# Quad-Stage-Prototype_FPGA_V1_0.net
KiCad netlist of a schematic drawn in Altium Designer
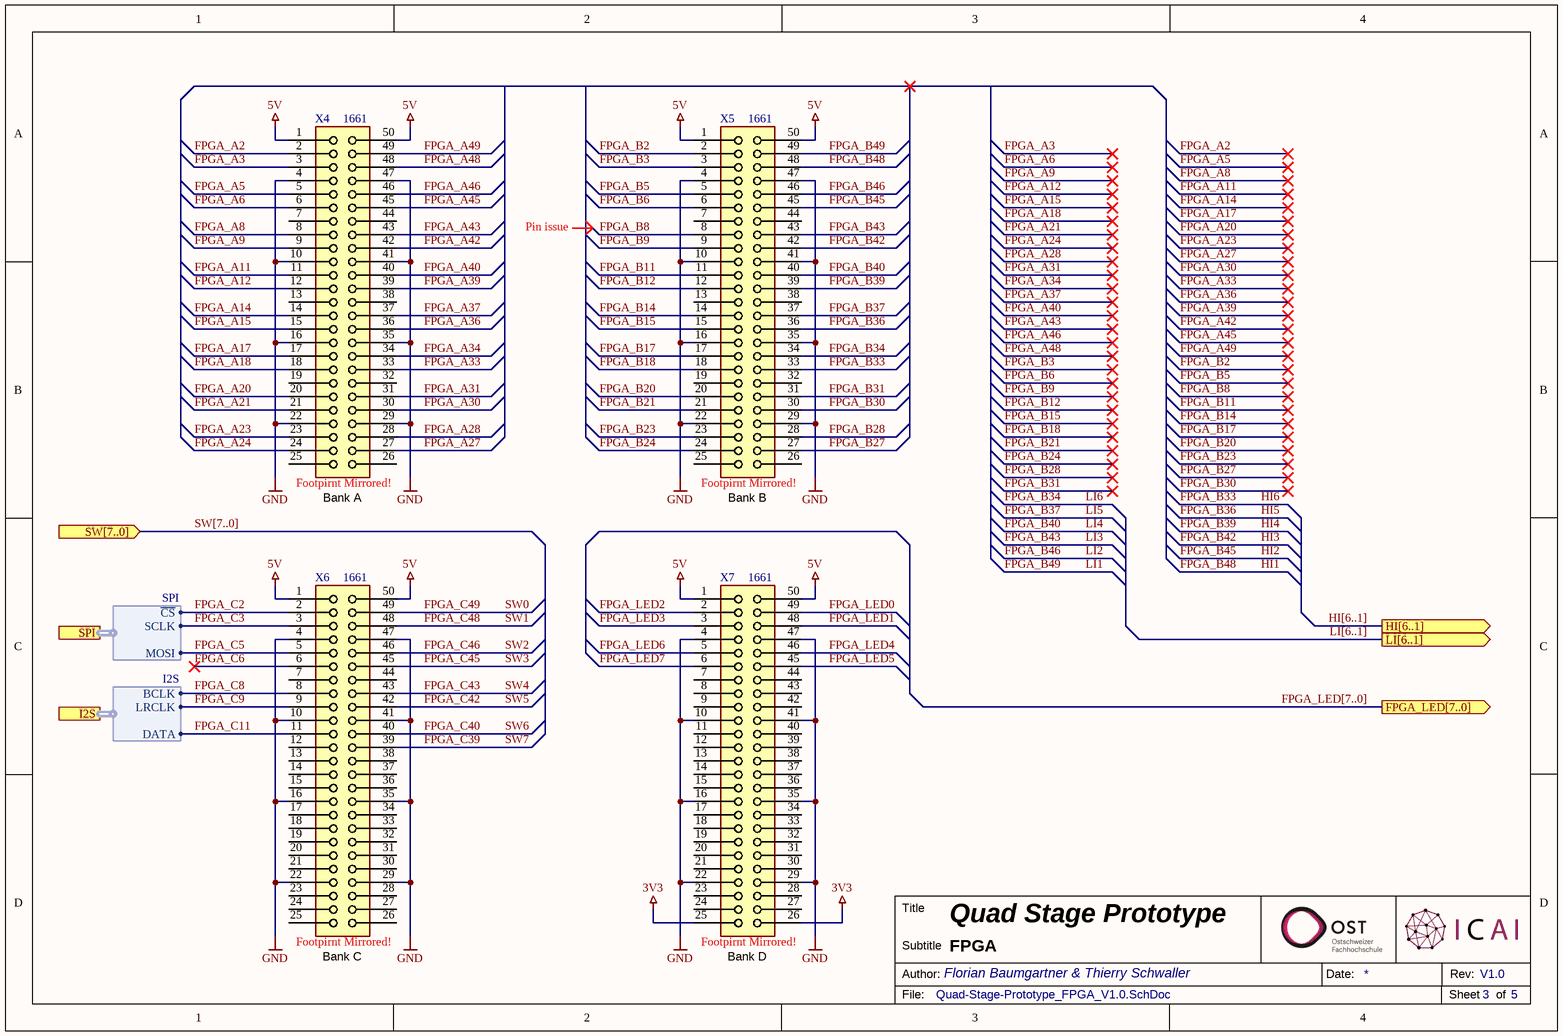
[diagram p0: Quad-Stage-Prototype_FPGA_V1.0.SchDoc]

(export (version "E")
  (design (tool "Eeschema 10.0.6"))
  (components
    (comp (ref "X4")
      (value "1661")
      (footprint "SMD Connector (1661)")
      (description "Board-to-Board Connector (Receptacle)")
      (libsource (lib "Quad-Stage-Prototype") (part "X-4UCON_1661"))
    )
    (comp (ref "X5")
      (value "1661")
      (footprint "SMD Connector (1661)")
      (description "Board-to-Board Connector (Receptacle)")
      (libsource (lib "Quad-Stage-Prototype") (part "X-4UCON_1661"))
    )
    (comp (ref "X6")
      (value "1661")
      (footprint "SMD Connector (1661)")
      (description "Board-to-Board Connector (Receptacle)")
      (libsource (lib "Quad-Stage-Prototype") (part "X-4UCON_1661"))
    )
    (comp (ref "X7")
      (value "1661")
      (footprint "SMD Connector (1661)")
      (description "Board-to-Board Connector (Receptacle)")
      (libsource (lib "Quad-Stage-Prototype") (part "X-4UCON_1661"))
    )
  )
  (nets
    (net (code "3") (name "/FPGA_A2") (class "Default")
      (node (ref "X4") (pin "2") (pinfunction "2_2") (pintype "passive"))
    )
    (net (code "4") (name "/FPGA_A3") (class "Default")
      (node (ref "X4") (pin "3") (pinfunction "3_3") (pintype "passive"))
    )
    (net (code "5") (name "/FPGA_A5") (class "Default")
      (node (ref "X4") (pin "5") (pinfunction "5_5") (pintype "passive"))
    )
    (net (code "6") (name "/FPGA_A6") (class "Default")
      (node (ref "X4") (pin "6") (pinfunction "6_6") (pintype "passive"))
    )
    (net (code "7") (name "/FPGA_A8") (class "Default")
      (node (ref "X4") (pin "8") (pinfunction "8_8") (pintype "passive"))
    )
    (net (code "8") (name "/FPGA_A9") (class "Default")
      (node (ref "X4") (pin "9") (pinfunction "9_9") (pintype "passive"))
    )
    (net (code "9") (name "/FPGA_A11") (class "Default")
      (node (ref "X4") (pin "11") (pinfunction "11_11") (pintype "passive"))
    )
    (net (code "10") (name "/FPGA_A12") (class "Default")
      (node (ref "X4") (pin "12") (pinfunction "12_12") (pintype "passive"))
    )
    (net (code "11") (name "/FPGA_A14") (class "Default")
      (node (ref "X4") (pin "14") (pinfunction "14_14") (pintype "passive"))
    )
    (net (code "12") (name "/FPGA_A15") (class "Default")
      (node (ref "X4") (pin "15") (pinfunction "15_15") (pintype "passive"))
    )
    (net (code "13") (name "/FPGA_A17") (class "Default")
      (node (ref "X4") (pin "17") (pinfunction "17_17") (pintype "passive"))
    )
    (net (code "14") (name "/FPGA_A18") (class "Default")
      (node (ref "X4") (pin "18") (pinfunction "18_18") (pintype "passive"))
    )
    (net (code "15") (name "/FPGA_A20") (class "Default")
      (node (ref "X4") (pin "20") (pinfunction "20_20") (pintype "passive"))
    )
    (net (code "16") (name "/FPGA_A21") (class "Default")
      (node (ref "X4") (pin "21") (pinfunction "21_21") (pintype "passive"))
    )
    (net (code "17") (name "/FPGA_A23") (class "Default")
      (node (ref "X4") (pin "23") (pinfunction "23_23") (pintype "passive"))
    )
    (net (code "18") (name "/FPGA_A24") (class "Default")
      (node (ref "X4") (pin "24") (pinfunction "24_24") (pintype "passive"))
    )
    (net (code "19") (name "/FPGA_A27") (class "Default")
      (node (ref "X4") (pin "27") (pinfunction "27_27") (pintype "passive"))
    )
    (net (code "20") (name "/FPGA_A28") (class "Default")
      (node (ref "X4") (pin "28") (pinfunction "28_28") (pintype "passive"))
    )
    (net (code "21") (name "/FPGA_A30") (class "Default")
      (node (ref "X4") (pin "30") (pinfunction "30_30") (pintype "passive"))
    )
    (net (code "22") (name "/FPGA_A31") (class "Default")
      (node (ref "X4") (pin "31") (pinfunction "31_31") (pintype "passive"))
    )
    (net (code "23") (name "/FPGA_A33") (class "Default")
      (node (ref "X4") (pin "33") (pinfunction "33_33") (pintype "passive"))
    )
    (net (code "24") (name "/FPGA_A34") (class "Default")
      (node (ref "X4") (pin "34") (pinfunction "34_34") (pintype "passive"))
    )
    (net (code "25") (name "/FPGA_A36") (class "Default")
      (node (ref "X4") (pin "36") (pinfunction "36_36") (pintype "passive"))
    )
    (net (code "26") (name "/FPGA_A37") (class "Default")
      (node (ref "X4") (pin "37") (pinfunction "37_37") (pintype "passive"))
    )
    (net (code "27") (name "/FPGA_A39") (class "Default")
      (node (ref "X4") (pin "39") (pinfunction "39_39") (pintype "passive"))
    )
    (net (code "28") (name "/FPGA_A40") (class "Default")
      (node (ref "X4") (pin "40") (pinfunction "40_40") (pintype "passive"))
    )
    (net (code "29") (name "/FPGA_A42") (class "Default")
      (node (ref "X4") (pin "42") (pinfunction "42_42") (pintype "passive"))
    )
    (net (code "30") (name "/FPGA_A43") (class "Default")
      (node (ref "X4") (pin "43") (pinfunction "43_43") (pintype "passive"))
    )
    (net (code "31") (name "/FPGA_A45") (class "Default")
      (node (ref "X4") (pin "45") (pinfunction "45_45") (pintype "passive"))
    )
    (net (code "32") (name "/FPGA_A46") (class "Default")
      (node (ref "X4") (pin "46") (pinfunction "46_46") (pintype "passive"))
    )
    (net (code "33") (name "/FPGA_A48") (class "Default")
      (node (ref "X4") (pin "48") (pinfunction "48_48") (pintype "passive+no_connect"))
    )
    (net (code "34") (name "/FPGA_A49") (class "Default")
      (node (ref "X4") (pin "49") (pinfunction "49_49") (pintype "passive"))
    )
    (net (code "35") (name "/FPGA_B2") (class "Default")
      (node (ref "X5") (pin "2") (pinfunction "2_2") (pintype "passive"))
    )
    (net (code "36") (name "/FPGA_B3") (class "Default")
      (node (ref "X5") (pin "3") (pinfunction "3_3") (pintype "passive+no_connect"))
    )
    (net (code "37") (name "/FPGA_B5") (class "Default")
      (node (ref "X5") (pin "5") (pinfunction "5_5") (pintype "passive"))
    )
    (net (code "38") (name "/FPGA_B6") (class "Default")
      (node (ref "X5") (pin "6") (pinfunction "6_6") (pintype "passive+no_connect"))
    )
    (net (code "39") (name "/FPGA_B8") (class "Default")
      (node (ref "X5") (pin "8") (pinfunction "8_8") (pintype "passive"))
    )
    (net (code "40") (name "/FPGA_B9") (class "Default")
      (node (ref "X5") (pin "9") (pinfunction "9_9") (pintype "passive+no_connect"))
    )
    (net (code "41") (name "/FPGA_B11") (class "Default")
      (node (ref "X5") (pin "11") (pinfunction "11_11") (pintype "passive"))
    )
    (net (code "42") (name "/FPGA_B12") (class "Default")
      (node (ref "X5") (pin "12") (pinfunction "12_12") (pintype "passive+no_connect"))
    )
    (net (code "43") (name "/FPGA_B14") (class "Default")
      (node (ref "X5") (pin "14") (pinfunction "14_14") (pintype "passive+no_connect"))
    )
    (net (code "44") (name "/FPGA_B15") (class "Default")
      (node (ref "X5") (pin "15") (pinfunction "15_15") (pintype "passive+no_connect"))
    )
    (net (code "45") (name "/FPGA_B17") (class "Default")
      (node (ref "X5") (pin "17") (pinfunction "17_17") (pintype "passive+no_connect"))
    )
    (net (code "46") (name "/FPGA_B18") (class "Default")
      (node (ref "X5") (pin "18") (pinfunction "18_18") (pintype "passive+no_connect"))
    )
    (net (code "47") (name "/FPGA_B20") (class "Default")
      (node (ref "X5") (pin "20") (pinfunction "20_20") (pintype "passive+no_connect"))
    )
    (net (code "48") (name "/FPGA_B21") (class "Default")
      (node (ref "X5") (pin "21") (pinfunction "21_21") (pintype "passive+no_connect"))
    )
    (net (code "49") (name "/FPGA_B23") (class "Default")
      (node (ref "X5") (pin "23") (pinfunction "23_23") (pintype "passive+no_connect"))
    )
    (net (code "50") (name "/FPGA_B24") (class "Default")
      (node (ref "X5") (pin "24") (pinfunction "24_24") (pintype "passive+no_connect"))
    )
    (net (code "51") (name "/FPGA_B27") (class "Default")
      (node (ref "X5") (pin "27") (pinfunction "27_27") (pintype "passive+no_connect"))
    )
    (net (code "52") (name "/FPGA_B28") (class "Default")
      (node (ref "X5") (pin "28") (pinfunction "28_28") (pintype "passive+no_connect"))
    )
    (net (code "53") (name "/FPGA_B30") (class "Default")
      (node (ref "X5") (pin "30") (pinfunction "30_30") (pintype "passive+no_connect"))
    )
    (net (code "54") (name "/FPGA_B31") (class "Default")
      (node (ref "X5") (pin "31") (pinfunction "31_31") (pintype "passive+no_connect"))
    )
    (net (code "55") (name "/FPGA_C2") (class "Default")
      (node (ref "X6") (pin "2") (pinfunction "2_2") (pintype "passive"))
    )
    (net (code "56") (name "/FPGA_C3") (class "Default")
      (node (ref "X6") (pin "3") (pinfunction "3_3") (pintype "passive"))
    )
    (net (code "57") (name "/FPGA_C5") (class "Default")
      (node (ref "X6") (pin "5") (pinfunction "5_5") (pintype "passive"))
    )
    (net (code "58") (name "/FPGA_C6") (class "Default")
      (node (ref "X6") (pin "6") (pinfunction "6_6") (pintype "passive+no_connect"))
    )
    (net (code "59") (name "/FPGA_C8") (class "Default")
      (node (ref "X6") (pin "8") (pinfunction "8_8") (pintype "passive"))
    )
    (net (code "60") (name "/FPGA_C9") (class "Default")
      (node (ref "X6") (pin "9") (pinfunction "9_9") (pintype "passive"))
    )
    (net (code "61") (name "/FPGA_C11") (class "Default")
      (node (ref "X6") (pin "11") (pinfunction "11_11") (pintype "passive"))
    )
    (net (code "62") (name "/FPGA_LED0") (class "Default")
      (node (ref "X7") (pin "49") (pinfunction "49_49") (pintype "passive"))
    )
    (net (code "63") (name "/FPGA_LED1") (class "Default")
      (node (ref "X7") (pin "48") (pinfunction "48_48") (pintype "passive"))
    )
    (net (code "64") (name "/FPGA_LED2") (class "Default")
      (node (ref "X7") (pin "2") (pinfunction "2_2") (pintype "passive"))
    )
    (net (code "65") (name "/FPGA_LED3") (class "Default")
      (node (ref "X7") (pin "3") (pinfunction "3_3") (pintype "passive"))
    )
    (net (code "66") (name "/FPGA_LED4") (class "Default")
      (node (ref "X7") (pin "46") (pinfunction "46_46") (pintype "passive"))
    )
    (net (code "67") (name "/FPGA_LED5") (class "Default")
      (node (ref "X7") (pin "45") (pinfunction "45_45") (pintype "passive"))
    )
    (net (code "68") (name "/FPGA_LED6") (class "Default")
      (node (ref "X7") (pin "5") (pinfunction "5_5") (pintype "passive"))
    )
    (net (code "69") (name "/FPGA_LED7") (class "Default")
      (node (ref "X7") (pin "6") (pinfunction "6_6") (pintype "passive"))
    )
    (net (code "71") (name "/HI1") (class "Default")
      (node (ref "X5") (pin "48") (pinfunction "48_48") (pintype "passive"))
    )
    (net (code "72") (name "/HI2") (class "Default")
      (node (ref "X5") (pin "45") (pinfunction "45_45") (pintype "passive"))
    )
    (net (code "73") (name "/HI3") (class "Default")
      (node (ref "X5") (pin "42") (pinfunction "42_42") (pintype "passive"))
    )
    (net (code "74") (name "/HI4") (class "Default")
      (node (ref "X5") (pin "39") (pinfunction "39_39") (pintype "passive"))
    )
    (net (code "75") (name "/HI5") (class "Default")
      (node (ref "X5") (pin "36") (pinfunction "36_36") (pintype "passive"))
    )
    (net (code "76") (name "/HI6") (class "Default")
      (node (ref "X5") (pin "33") (pinfunction "33_33") (pintype "passive"))
    )
    (net (code "78") (name "/LI1") (class "Default")
      (node (ref "X5") (pin "49") (pinfunction "49_49") (pintype "passive"))
    )
    (net (code "79") (name "/LI2") (class "Default")
      (node (ref "X5") (pin "46") (pinfunction "46_46") (pintype "passive"))
    )
    (net (code "80") (name "/LI3") (class "Default")
      (node (ref "X5") (pin "43") (pinfunction "43_43") (pintype "passive"))
    )
    (net (code "81") (name "/LI4") (class "Default")
      (node (ref "X5") (pin "40") (pinfunction "40_40") (pintype "passive"))
    )
    (net (code "82") (name "/LI5") (class "Default")
      (node (ref "X5") (pin "37") (pinfunction "37_37") (pintype "passive"))
    )
    (net (code "83") (name "/LI6") (class "Default")
      (node (ref "X5") (pin "34") (pinfunction "34_34") (pintype "passive"))
    )
    (net (code "85") (name "/SW0") (class "Default")
      (node (ref "X6") (pin "49") (pinfunction "49_49") (pintype "passive"))
    )
    (net (code "86") (name "/SW1") (class "Default")
      (node (ref "X6") (pin "48") (pinfunction "48_48") (pintype "passive"))
    )
    (net (code "87") (name "/SW2") (class "Default")
      (node (ref "X6") (pin "46") (pinfunction "46_46") (pintype "passive"))
    )
    (net (code "88") (name "/SW3") (class "Default")
      (node (ref "X6") (pin "45") (pinfunction "45_45") (pintype "passive"))
    )
    (net (code "89") (name "/SW4") (class "Default")
      (node (ref "X6") (pin "43") (pinfunction "43_43") (pintype "passive"))
    )
    (net (code "90") (name "/SW5") (class "Default")
      (node (ref "X6") (pin "42") (pinfunction "42_42") (pintype "passive"))
    )
    (net (code "91") (name "/SW6") (class "Default")
      (node (ref "X6") (pin "40") (pinfunction "40_40") (pintype "passive"))
    )
    (net (code "92") (name "/SW7") (class "Default")
      (node (ref "X6") (pin "39") (pinfunction "39_39") (pintype "passive"))
    )
    (net (code "96") (name "3V3") (class "Default")
      (node (ref "X7") (pin "25") (pinfunction "25_25") (pintype "passive"))
      (node (ref "X7") (pin "26") (pinfunction "26_26") (pintype "passive"))
    )
    (net (code "97") (name "5V") (class "Default")
      (node (ref "X4") (pin "1") (pinfunction "1_1") (pintype "passive"))
      (node (ref "X4") (pin "50") (pinfunction "50_50") (pintype "passive"))
      (node (ref "X5") (pin "1") (pinfunction "1_1") (pintype "passive"))
      (node (ref "X5") (pin "50") (pinfunction "50_50") (pintype "passive"))
      (node (ref "X6") (pin "1") (pinfunction "1_1") (pintype "passive"))
      (node (ref "X6") (pin "50") (pinfunction "50_50") (pintype "passive"))
      (node (ref "X7") (pin "1") (pinfunction "1_1") (pintype "passive"))
      (node (ref "X7") (pin "50") (pinfunction "50_50") (pintype "passive"))
    )
    (net (code "98") (name "GND") (class "Default")
      (node (ref "X4") (pin "10") (pinfunction "10_10") (pintype "passive"))
      (node (ref "X4") (pin "16") (pinfunction "16_16") (pintype "passive"))
      (node (ref "X4") (pin "22") (pinfunction "22_22") (pintype "passive"))
      (node (ref "X4") (pin "29") (pinfunction "29_29") (pintype "passive"))
      (node (ref "X4") (pin "35") (pinfunction "35_35") (pintype "passive"))
      (node (ref "X4") (pin "4") (pinfunction "4_4") (pintype "passive"))
      (node (ref "X4") (pin "41") (pinfunction "41_41") (pintype "passive"))
      (node (ref "X4") (pin "47") (pinfunction "47_47") (pintype "passive"))
      (node (ref "X5") (pin "10") (pinfunction "10_10") (pintype "passive"))
      (node (ref "X5") (pin "16") (pinfunction "16_16") (pintype "passive"))
      (node (ref "X5") (pin "22") (pinfunction "22_22") (pintype "passive"))
      (node (ref "X5") (pin "29") (pinfunction "29_29") (pintype "passive"))
      (node (ref "X5") (pin "35") (pinfunction "35_35") (pintype "passive"))
      (node (ref "X5") (pin "4") (pinfunction "4_4") (pintype "passive"))
      (node (ref "X5") (pin "41") (pinfunction "41_41") (pintype "passive"))
      (node (ref "X5") (pin "47") (pinfunction "47_47") (pintype "passive"))
      (node (ref "X6") (pin "10") (pinfunction "10_10") (pintype "passive"))
      (node (ref "X6") (pin "16") (pinfunction "16_16") (pintype "passive"))
      (node (ref "X6") (pin "22") (pinfunction "22_22") (pintype "passive"))
      (node (ref "X6") (pin "29") (pinfunction "29_29") (pintype "passive"))
      (node (ref "X6") (pin "35") (pinfunction "35_35") (pintype "passive"))
      (node (ref "X6") (pin "4") (pinfunction "4_4") (pintype "passive"))
      (node (ref "X6") (pin "41") (pinfunction "41_41") (pintype "passive"))
      (node (ref "X6") (pin "47") (pinfunction "47_47") (pintype "passive"))
      (node (ref "X7") (pin "10") (pinfunction "10_10") (pintype "passive"))
      (node (ref "X7") (pin "16") (pinfunction "16_16") (pintype "passive"))
      (node (ref "X7") (pin "22") (pinfunction "22_22") (pintype "passive"))
      (node (ref "X7") (pin "29") (pinfunction "29_29") (pintype "passive"))
      (node (ref "X7") (pin "35") (pinfunction "35_35") (pintype "passive"))
      (node (ref "X7") (pin "4") (pinfunction "4_4") (pintype "passive"))
      (node (ref "X7") (pin "41") (pinfunction "41_41") (pintype "passive"))
      (node (ref "X7") (pin "47") (pinfunction "47_47") (pintype "passive"))
    )
    (net (code "99") (name "unconnected-(X4-Pad7)") (class "Default")
      (node (ref "X4") (pin "7") (pinfunction "7_7") (pintype "passive"))
    )
    (net (code "100") (name "unconnected-(X4-Pad13)") (class "Default")
      (node (ref "X4") (pin "13") (pinfunction "13_13") (pintype "passive"))
    )
    (net (code "101") (name "unconnected-(X4-Pad19)") (class "Default")
      (node (ref "X4") (pin "19") (pinfunction "19_19") (pintype "passive"))
    )
    (net (code "102") (name "unconnected-(X4-Pad25)") (class "Default")
      (node (ref "X4") (pin "25") (pinfunction "25_25") (pintype "passive"))
    )
    (net (code "103") (name "unconnected-(X4-Pad26)") (class "Default")
      (node (ref "X4") (pin "26") (pinfunction "26_26") (pintype "passive"))
    )
    (net (code "104") (name "unconnected-(X4-Pad32)") (class "Default")
      (node (ref "X4") (pin "32") (pinfunction "32_32") (pintype "passive"))
    )
    (net (code "105") (name "unconnected-(X4-Pad38)") (class "Default")
      (node (ref "X4") (pin "38") (pinfunction "38_38") (pintype "passive"))
    )
    (net (code "106") (name "unconnected-(X4-Pad44)") (class "Default")
      (node (ref "X4") (pin "44") (pinfunction "44_44") (pintype "passive"))
    )
    (net (code "107") (name "unconnected-(X5-Pad7)") (class "Default")
      (node (ref "X5") (pin "7") (pinfunction "7_7") (pintype "passive"))
    )
    (net (code "108") (name "unconnected-(X5-Pad13)") (class "Default")
      (node (ref "X5") (pin "13") (pinfunction "13_13") (pintype "passive"))
    )
    (net (code "109") (name "unconnected-(X5-Pad19)") (class "Default")
      (node (ref "X5") (pin "19") (pinfunction "19_19") (pintype "passive"))
    )
    (net (code "110") (name "unconnected-(X5-Pad25)") (class "Default")
      (node (ref "X5") (pin "25") (pinfunction "25_25") (pintype "passive"))
    )
    (net (code "111") (name "unconnected-(X5-Pad26)") (class "Default")
      (node (ref "X5") (pin "26") (pinfunction "26_26") (pintype "passive"))
    )
    (net (code "112") (name "unconnected-(X5-Pad32)") (class "Default")
      (node (ref "X5") (pin "32") (pinfunction "32_32") (pintype "passive"))
    )
    (net (code "113") (name "unconnected-(X5-Pad38)") (class "Default")
      (node (ref "X5") (pin "38") (pinfunction "38_38") (pintype "passive"))
    )
    (net (code "114") (name "unconnected-(X5-Pad44)") (class "Default")
      (node (ref "X5") (pin "44") (pinfunction "44_44") (pintype "passive"))
    )
    (net (code "115") (name "unconnected-(X6-Pad7)") (class "Default")
      (node (ref "X6") (pin "7") (pinfunction "7_7") (pintype "passive"))
    )
    (net (code "116") (name "unconnected-(X6-Pad12)") (class "Default")
      (node (ref "X6") (pin "12") (pinfunction "12_12") (pintype "passive"))
    )
    (net (code "117") (name "unconnected-(X6-Pad13)") (class "Default")
      (node (ref "X6") (pin "13") (pinfunction "13_13") (pintype "passive"))
    )
    (net (code "118") (name "unconnected-(X6-Pad14)") (class "Default")
      (node (ref "X6") (pin "14") (pinfunction "14_14") (pintype "passive"))
    )
    (net (code "119") (name "unconnected-(X6-Pad15)") (class "Default")
      (node (ref "X6") (pin "15") (pinfunction "15_15") (pintype "passive"))
    )
    (net (code "120") (name "unconnected-(X6-Pad17)") (class "Default")
      (node (ref "X6") (pin "17") (pinfunction "17_17") (pintype "passive"))
    )
    (net (code "121") (name "unconnected-(X6-Pad18)") (class "Default")
      (node (ref "X6") (pin "18") (pinfunction "18_18") (pintype "passive"))
    )
    (net (code "122") (name "unconnected-(X6-Pad19)") (class "Default")
      (node (ref "X6") (pin "19") (pinfunction "19_19") (pintype "passive"))
    )
    (net (code "123") (name "unconnected-(X6-Pad20)") (class "Default")
      (node (ref "X6") (pin "20") (pinfunction "20_20") (pintype "passive"))
    )
    (net (code "124") (name "unconnected-(X6-Pad21)") (class "Default")
      (node (ref "X6") (pin "21") (pinfunction "21_21") (pintype "passive"))
    )
    (net (code "125") (name "unconnected-(X6-Pad23)") (class "Default")
      (node (ref "X6") (pin "23") (pinfunction "23_23") (pintype "passive"))
    )
    (net (code "126") (name "unconnected-(X6-Pad24)") (class "Default")
      (node (ref "X6") (pin "24") (pinfunction "24_24") (pintype "passive"))
    )
    (net (code "127") (name "unconnected-(X6-Pad25)") (class "Default")
      (node (ref "X6") (pin "25") (pinfunction "25_25") (pintype "passive"))
    )
    (net (code "128") (name "unconnected-(X6-Pad26)") (class "Default")
      (node (ref "X6") (pin "26") (pinfunction "26_26") (pintype "passive"))
    )
    (net (code "129") (name "unconnected-(X6-Pad27)") (class "Default")
      (node (ref "X6") (pin "27") (pinfunction "27_27") (pintype "passive"))
    )
    (net (code "130") (name "unconnected-(X6-Pad28)") (class "Default")
      (node (ref "X6") (pin "28") (pinfunction "28_28") (pintype "passive"))
    )
    (net (code "131") (name "unconnected-(X6-Pad30)") (class "Default")
      (node (ref "X6") (pin "30") (pinfunction "30_30") (pintype "passive"))
    )
    (net (code "132") (name "unconnected-(X6-Pad31)") (class "Default")
      (node (ref "X6") (pin "31") (pinfunction "31_31") (pintype "passive"))
    )
    (net (code "133") (name "unconnected-(X6-Pad32)") (class "Default")
      (node (ref "X6") (pin "32") (pinfunction "32_32") (pintype "passive"))
    )
    (net (code "134") (name "unconnected-(X6-Pad33)") (class "Default")
      (node (ref "X6") (pin "33") (pinfunction "33_33") (pintype "passive"))
    )
    (net (code "135") (name "unconnected-(X6-Pad34)") (class "Default")
      (node (ref "X6") (pin "34") (pinfunction "34_34") (pintype "passive"))
    )
    (net (code "136") (name "unconnected-(X6-Pad36)") (class "Default")
      (node (ref "X6") (pin "36") (pinfunction "36_36") (pintype "passive"))
    )
    (net (code "137") (name "unconnected-(X6-Pad37)") (class "Default")
      (node (ref "X6") (pin "37") (pinfunction "37_37") (pintype "passive"))
    )
    (net (code "138") (name "unconnected-(X6-Pad38)") (class "Default")
      (node (ref "X6") (pin "38") (pinfunction "38_38") (pintype "passive"))
    )
    (net (code "139") (name "unconnected-(X6-Pad44)") (class "Default")
      (node (ref "X6") (pin "44") (pinfunction "44_44") (pintype "passive"))
    )
    (net (code "140") (name "unconnected-(X7-Pad7)") (class "Default")
      (node (ref "X7") (pin "7") (pinfunction "7_7") (pintype "passive"))
    )
    (net (code "141") (name "unconnected-(X7-Pad8)") (class "Default")
      (node (ref "X7") (pin "8") (pinfunction "8_8") (pintype "passive"))
    )
    (net (code "142") (name "unconnected-(X7-Pad9)") (class "Default")
      (node (ref "X7") (pin "9") (pinfunction "9_9") (pintype "passive"))
    )
    (net (code "143") (name "unconnected-(X7-Pad11)") (class "Default")
      (node (ref "X7") (pin "11") (pinfunction "11_11") (pintype "passive"))
    )
    (net (code "144") (name "unconnected-(X7-Pad12)") (class "Default")
      (node (ref "X7") (pin "12") (pinfunction "12_12") (pintype "passive"))
    )
    (net (code "145") (name "unconnected-(X7-Pad13)") (class "Default")
      (node (ref "X7") (pin "13") (pinfunction "13_13") (pintype "passive"))
    )
    (net (code "146") (name "unconnected-(X7-Pad14)") (class "Default")
      (node (ref "X7") (pin "14") (pinfunction "14_14") (pintype "passive"))
    )
    (net (code "147") (name "unconnected-(X7-Pad15)") (class "Default")
      (node (ref "X7") (pin "15") (pinfunction "15_15") (pintype "passive"))
    )
    (net (code "148") (name "unconnected-(X7-Pad17)") (class "Default")
      (node (ref "X7") (pin "17") (pinfunction "17_17") (pintype "passive"))
    )
    (net (code "149") (name "unconnected-(X7-Pad18)") (class "Default")
      (node (ref "X7") (pin "18") (pinfunction "18_18") (pintype "passive"))
    )
    (net (code "150") (name "unconnected-(X7-Pad19)") (class "Default")
      (node (ref "X7") (pin "19") (pinfunction "19_19") (pintype "passive"))
    )
    (net (code "151") (name "unconnected-(X7-Pad20)") (class "Default")
      (node (ref "X7") (pin "20") (pinfunction "20_20") (pintype "passive"))
    )
    (net (code "152") (name "unconnected-(X7-Pad21)") (class "Default")
      (node (ref "X7") (pin "21") (pinfunction "21_21") (pintype "passive"))
    )
    (net (code "153") (name "unconnected-(X7-Pad23)") (class "Default")
      (node (ref "X7") (pin "23") (pinfunction "23_23") (pintype "passive"))
    )
    (net (code "154") (name "unconnected-(X7-Pad24)") (class "Default")
      (node (ref "X7") (pin "24") (pinfunction "24_24") (pintype "passive"))
    )
    (net (code "155") (name "unconnected-(X7-Pad27)") (class "Default")
      (node (ref "X7") (pin "27") (pinfunction "27_27") (pintype "passive"))
    )
    (net (code "156") (name "unconnected-(X7-Pad28)") (class "Default")
      (node (ref "X7") (pin "28") (pinfunction "28_28") (pintype "passive"))
    )
    (net (code "157") (name "unconnected-(X7-Pad30)") (class "Default")
      (node (ref "X7") (pin "30") (pinfunction "30_30") (pintype "passive"))
    )
    (net (code "158") (name "unconnected-(X7-Pad31)") (class "Default")
      (node (ref "X7") (pin "31") (pinfunction "31_31") (pintype "passive"))
    )
    (net (code "159") (name "unconnected-(X7-Pad32)") (class "Default")
      (node (ref "X7") (pin "32") (pinfunction "32_32") (pintype "passive"))
    )
    (net (code "160") (name "unconnected-(X7-Pad33)") (class "Default")
      (node (ref "X7") (pin "33") (pinfunction "33_33") (pintype "passive"))
    )
    (net (code "161") (name "unconnected-(X7-Pad34)") (class "Default")
      (node (ref "X7") (pin "34") (pinfunction "34_34") (pintype "passive"))
    )
    (net (code "162") (name "unconnected-(X7-Pad36)") (class "Default")
      (node (ref "X7") (pin "36") (pinfunction "36_36") (pintype "passive"))
    )
    (net (code "163") (name "unconnected-(X7-Pad37)") (class "Default")
      (node (ref "X7") (pin "37") (pinfunction "37_37") (pintype "passive"))
    )
    (net (code "164") (name "unconnected-(X7-Pad38)") (class "Default")
      (node (ref "X7") (pin "38") (pinfunction "38_38") (pintype "passive"))
    )
    (net (code "165") (name "unconnected-(X7-Pad39)") (class "Default")
      (node (ref "X7") (pin "39") (pinfunction "39_39") (pintype "passive"))
    )
    (net (code "166") (name "unconnected-(X7-Pad40)") (class "Default")
      (node (ref "X7") (pin "40") (pinfunction "40_40") (pintype "passive"))
    )
    (net (code "167") (name "unconnected-(X7-Pad42)") (class "Default")
      (node (ref "X7") (pin "42") (pinfunction "42_42") (pintype "passive"))
    )
    (net (code "168") (name "unconnected-(X7-Pad43)") (class "Default")
      (node (ref "X7") (pin "43") (pinfunction "43_43") (pintype "passive"))
    )
    (net (code "169") (name "unconnected-(X7-Pad44)") (class "Default")
      (node (ref "X7") (pin "44") (pinfunction "44_44") (pintype "passive"))
    )
  )
)
